# ExpandBoard-103-003.net
KiCad netlist of a schematic drawn in Altium Designer
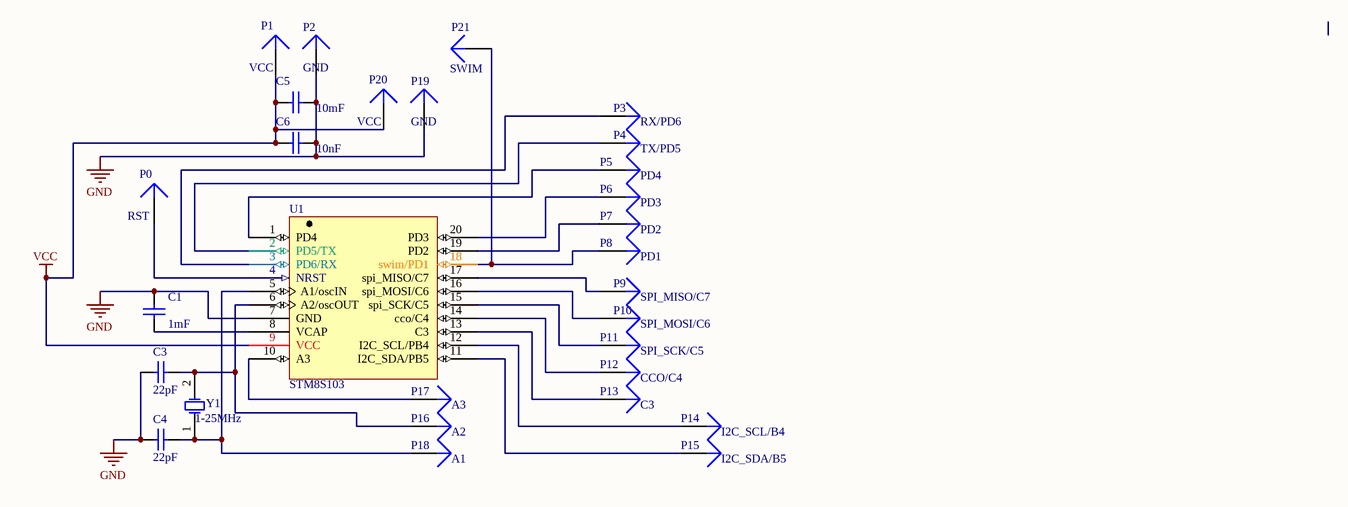
[diagram p0: ExpandBoard-103-003.SchDoc]

(export (version "E")
  (design (tool "Eeschema 10.0.6"))
  (components
    (comp (ref "C1")
      (value "1mF")
      (footprint "CAPC0805(2012)75_L")
      (libsource (lib "GnericSymbols") (part "CAP"))
    )
    (comp (ref "C3")
      (value "22pF")
      (footprint "CAPC0805(2012)75_N")
      (libsource (lib "GnericSymbols") (part "CAP"))
    )
    (comp (ref "C4")
      (value "22pF")
      (footprint "CAPC0805(2012)75_N")
      (libsource (lib "GnericSymbols") (part "CAP"))
    )
    (comp (ref "C5")
      (value "10mF")
      (footprint "CAPC0805(2012)75_L")
      (libsource (lib "GnericSymbols") (part "CAP"))
    )
    (comp (ref "C6")
      (value "10nF")
      (footprint "CAPC0805(2012)75_L")
      (libsource (lib "GnericSymbols") (part "CAP"))
    )
    (comp (ref "P0")
      (value "RST")
      (footprint "PIN1")
      (description "Plug")
      (fields (field (name "PUBLISHER") "Altium Limited"))
      (libsource (lib "Miscellaneous Connectors") (part "Plug"))
    )
    (comp (ref "P1")
      (value "VCC")
      (footprint "PIN1")
      (description "Plug")
      (fields (field (name "PUBLISHER") "Altium Limited"))
      (libsource (lib "Miscellaneous Connectors") (part "Plug"))
    )
    (comp (ref "P2")
      (value "GND")
      (footprint "PIN1")
      (description "Plug")
      (fields (field (name "PUBLISHER") "Altium Limited"))
      (libsource (lib "Miscellaneous Connectors") (part "Plug"))
    )
    (comp (ref "P3")
      (value "RX/PD6")
      (footprint "PIN1")
      (description "Plug")
      (fields (field (name "PUBLISHER") "Altium Limited"))
      (libsource (lib "Miscellaneous Connectors") (part "Plug"))
    )
    (comp (ref "P4")
      (value "TX/PD5")
      (footprint "PIN1")
      (description "Plug")
      (fields (field (name "PUBLISHER") "Altium Limited"))
      (libsource (lib "Miscellaneous Connectors") (part "Plug"))
    )
    (comp (ref "P5")
      (value "PD4")
      (footprint "PIN1")
      (description "Plug")
      (fields (field (name "PUBLISHER") "Altium Limited"))
      (libsource (lib "Miscellaneous Connectors") (part "Plug"))
    )
    (comp (ref "P6")
      (value "PD3")
      (footprint "PIN1")
      (description "Plug")
      (fields (field (name "PUBLISHER") "Altium Limited"))
      (libsource (lib "Miscellaneous Connectors") (part "Plug"))
    )
    (comp (ref "P7")
      (value "PD2")
      (footprint "PIN1")
      (description "Plug")
      (fields (field (name "PUBLISHER") "Altium Limited"))
      (libsource (lib "Miscellaneous Connectors") (part "Plug"))
    )
    (comp (ref "P8")
      (value "PD1")
      (footprint "PIN1")
      (description "Plug")
      (fields (field (name "PUBLISHER") "Altium Limited"))
      (libsource (lib "Miscellaneous Connectors") (part "Plug"))
    )
    (comp (ref "P9")
      (value "SPI_MISO/C7")
      (footprint "PIN1")
      (description "Plug")
      (fields (field (name "PUBLISHER") "Altium Limited"))
      (libsource (lib "Miscellaneous Connectors") (part "Plug"))
    )
    (comp (ref "P10")
      (value "SPI_MOSI/C6")
      (footprint "PIN1")
      (description "Plug")
      (fields (field (name "PUBLISHER") "Altium Limited"))
      (libsource (lib "Miscellaneous Connectors") (part "Plug"))
    )
    (comp (ref "P11")
      (value "SPI_SCK/C5")
      (footprint "PIN1")
      (description "Plug")
      (fields (field (name "PUBLISHER") "Altium Limited"))
      (libsource (lib "Miscellaneous Connectors") (part "Plug"))
    )
    (comp (ref "P12")
      (value "CCO/C4")
      (footprint "PIN1")
      (description "Plug")
      (fields (field (name "PUBLISHER") "Altium Limited"))
      (libsource (lib "Miscellaneous Connectors") (part "Plug"))
    )
    (comp (ref "P13")
      (value "C3")
      (footprint "PIN1")
      (description "Plug")
      (fields (field (name "PUBLISHER") "Altium Limited"))
      (libsource (lib "Miscellaneous Connectors") (part "Plug"))
    )
    (comp (ref "P14")
      (value "I2C_SCL/B4")
      (footprint "PIN1")
      (description "Plug")
      (fields (field (name "PUBLISHER") "Altium Limited"))
      (libsource (lib "Miscellaneous Connectors") (part "Plug"))
    )
    (comp (ref "P15")
      (value "I2C_SDA/B5")
      (footprint "PIN1")
      (description "Plug")
      (fields (field (name "PUBLISHER") "Altium Limited"))
      (libsource (lib "Miscellaneous Connectors") (part "Plug"))
    )
    (comp (ref "P16")
      (value "A2")
      (footprint "PIN1")
      (description "Plug")
      (fields (field (name "PUBLISHER") "Altium Limited"))
      (libsource (lib "Miscellaneous Connectors") (part "Plug"))
    )
    (comp (ref "P17")
      (value "A3")
      (footprint "PIN1")
      (description "Plug")
      (fields (field (name "PUBLISHER") "Altium Limited"))
      (libsource (lib "Miscellaneous Connectors") (part "Plug"))
    )
    (comp (ref "P18")
      (value "A1")
      (footprint "PIN1")
      (description "Plug")
      (fields (field (name "PUBLISHER") "Altium Limited"))
      (libsource (lib "Miscellaneous Connectors") (part "Plug"))
    )
    (comp (ref "P19")
      (value "GND")
      (footprint "PIN1")
      (description "Plug")
      (fields (field (name "PUBLISHER") "Altium Limited"))
      (libsource (lib "Miscellaneous Connectors") (part "Plug"))
    )
    (comp (ref "P20")
      (value "VCC")
      (footprint "PIN1")
      (description "Plug")
      (fields (field (name "PUBLISHER") "Altium Limited"))
      (libsource (lib "Miscellaneous Connectors") (part "Plug"))
    )
    (comp (ref "P21")
      (value "SWIM")
      (footprint "PIN1")
      (description "Plug")
      (fields (field (name "PUBLISHER") "Altium Limited"))
      (libsource (lib "Miscellaneous Connectors") (part "Plug"))
    )
    (comp (ref "U1")
      (value "STM8S103")
      (footprint "TSSOP20")
      (libsource (lib "PlatformLibrary") (part "STM8S103"))
    )
    (comp (ref "Y1")
      (value "1-25MHz")
      (footprint "3.2X1.6X1.1")
      (description "Crystal Oscillator")
      (fields (field (name "PUBLISHER") "Altium Limited"))
      (libsource (lib "Miscellaneous Devices") (part "XTAL"))
    )
  )
  (nets
    (net (code "1") (name "GND") (class "Default")
      (node (ref "C1") (pin "2") (pinfunction "2_2") (pintype "passive"))
      (node (ref "C3") (pin "2") (pinfunction "2_2") (pintype "passive"))
      (node (ref "C4") (pin "2") (pinfunction "2_2") (pintype "passive"))
      (node (ref "C5") (pin "1") (pinfunction "1_1") (pintype "passive"))
      (node (ref "C6") (pin "1") (pinfunction "1_1") (pintype "passive"))
      (node (ref "P19") (pin "1") (pinfunction "1_1") (pintype "passive"))
      (node (ref "P2") (pin "1") (pinfunction "1_1") (pintype "passive"))
      (node (ref "U1") (pin "7") (pinfunction "GND_7") (pintype "power_in"))
    )
    (net (code "2") (name "Net-(U1-A1{slash}oscIN)") (class "Default")
      (node (ref "C4") (pin "1") (pinfunction "1_1") (pintype "passive"))
      (node (ref "P18") (pin "1") (pinfunction "1_1") (pintype "passive"))
      (node (ref "U1") (pin "5") (pinfunction "A1/oscIN_5") (pintype "bidirectional"))
      (node (ref "Y1") (pin "1") (pinfunction "OSC1_1") (pintype "passive"))
    )
    (net (code "3") (name "Net-(U1-A2{slash}oscOUT)") (class "Default")
      (node (ref "C3") (pin "1") (pinfunction "1_1") (pintype "passive"))
      (node (ref "P16") (pin "1") (pinfunction "1_1") (pintype "passive"))
      (node (ref "U1") (pin "6") (pinfunction "A2/oscOUT_6") (pintype "bidirectional"))
      (node (ref "Y1") (pin "2") (pinfunction "OSC2_2") (pintype "passive"))
    )
    (net (code "4") (name "Net-(U1-A3)") (class "Default")
      (node (ref "P17") (pin "1") (pinfunction "1_1") (pintype "passive"))
      (node (ref "U1") (pin "10") (pinfunction "A3_10") (pintype "bidirectional"))
    )
    (net (code "5") (name "Net-(U1-C3)") (class "Default")
      (node (ref "P13") (pin "1") (pinfunction "1_1") (pintype "passive"))
      (node (ref "U1") (pin "13") (pinfunction "C3_13") (pintype "bidirectional"))
    )
    (net (code "6") (name "Net-(U1-I2C_SCL{slash}PB4)") (class "Default")
      (node (ref "P14") (pin "1") (pinfunction "1_1") (pintype "passive"))
      (node (ref "U1") (pin "12") (pinfunction "I2C_SCL/PB4_12") (pintype "bidirectional"))
    )
    (net (code "7") (name "Net-(U1-I2C_SDA{slash}PB5)") (class "Default")
      (node (ref "P15") (pin "1") (pinfunction "1_1") (pintype "passive"))
      (node (ref "U1") (pin "11") (pinfunction "I2C_SDA/PB5_11") (pintype "bidirectional"))
    )
    (net (code "8") (name "Net-(U1-NRST)") (class "Default")
      (node (ref "P0") (pin "1") (pinfunction "1_1") (pintype "passive"))
      (node (ref "U1") (pin "4") (pinfunction "NRST_4") (pintype "input"))
    )
    (net (code "9") (name "Net-(U1-PD2)") (class "Default")
      (node (ref "P7") (pin "1") (pinfunction "1_1") (pintype "passive"))
      (node (ref "U1") (pin "19") (pinfunction "PD2_19") (pintype "bidirectional"))
    )
    (net (code "10") (name "Net-(U1-PD3)") (class "Default")
      (node (ref "P6") (pin "1") (pinfunction "1_1") (pintype "passive"))
      (node (ref "U1") (pin "20") (pinfunction "PD3_20") (pintype "bidirectional"))
    )
    (net (code "11") (name "Net-(U1-PD4)") (class "Default")
      (node (ref "P5") (pin "1") (pinfunction "1_1") (pintype "passive"))
      (node (ref "U1") (pin "1") (pinfunction "PD4_1") (pintype "bidirectional"))
    )
    (net (code "12") (name "Net-(U1-PD5{slash}TX)") (class "Default")
      (node (ref "P4") (pin "1") (pinfunction "1_1") (pintype "passive"))
      (node (ref "U1") (pin "2") (pinfunction "PD5/TX_2") (pintype "bidirectional"))
    )
    (net (code "13") (name "Net-(U1-PD6{slash}RX)") (class "Default")
      (node (ref "P3") (pin "1") (pinfunction "1_1") (pintype "passive"))
      (node (ref "U1") (pin "3") (pinfunction "PD6/RX_3") (pintype "bidirectional"))
    )
    (net (code "14") (name "Net-(U1-VCAP)") (class "Default")
      (node (ref "C1") (pin "1") (pinfunction "1_1") (pintype "passive"))
      (node (ref "U1") (pin "8") (pinfunction "VCAP_8") (pintype "power_in"))
    )
    (net (code "15") (name "Net-(U1-cco{slash}C4)") (class "Default")
      (node (ref "P12") (pin "1") (pinfunction "1_1") (pintype "passive"))
      (node (ref "U1") (pin "14") (pinfunction "cco/C4_14") (pintype "bidirectional"))
    )
    (net (code "16") (name "Net-(U1-spi_MISO{slash}C7)") (class "Default")
      (node (ref "P9") (pin "1") (pinfunction "1_1") (pintype "passive"))
      (node (ref "U1") (pin "17") (pinfunction "spi_MISO/C7_17") (pintype "bidirectional"))
    )
    (net (code "17") (name "Net-(U1-spi_MOSI{slash}C6)") (class "Default")
      (node (ref "P10") (pin "1") (pinfunction "1_1") (pintype "passive"))
      (node (ref "U1") (pin "16") (pinfunction "spi_MOSI/C6_16") (pintype "bidirectional"))
    )
    (net (code "18") (name "Net-(U1-spi_SCK{slash}C5)") (class "Default")
      (node (ref "P11") (pin "1") (pinfunction "1_1") (pintype "passive"))
      (node (ref "U1") (pin "15") (pinfunction "spi_SCK/C5_15") (pintype "bidirectional"))
    )
    (net (code "19") (name "Net-(U1-swim{slash}PD1)") (class "Default")
      (node (ref "P21") (pin "1") (pinfunction "1_1") (pintype "passive"))
      (node (ref "P8") (pin "1") (pinfunction "1_1") (pintype "passive"))
      (node (ref "U1") (pin "18") (pinfunction "swim/PD1_18") (pintype "bidirectional"))
    )
    (net (code "20") (name "VCC") (class "Default")
      (node (ref "C5") (pin "2") (pinfunction "2_2") (pintype "passive"))
      (node (ref "C6") (pin "2") (pinfunction "2_2") (pintype "passive"))
      (node (ref "P1") (pin "1") (pinfunction "1_1") (pintype "passive"))
      (node (ref "P20") (pin "1") (pinfunction "1_1") (pintype "passive"))
      (node (ref "U1") (pin "9") (pinfunction "VCC_9") (pintype "power_in"))
    )
  )
)
